# SCH_Glucosan2-DetectorSide.net
KiCad netlist of a schematic drawn in EasyEDA
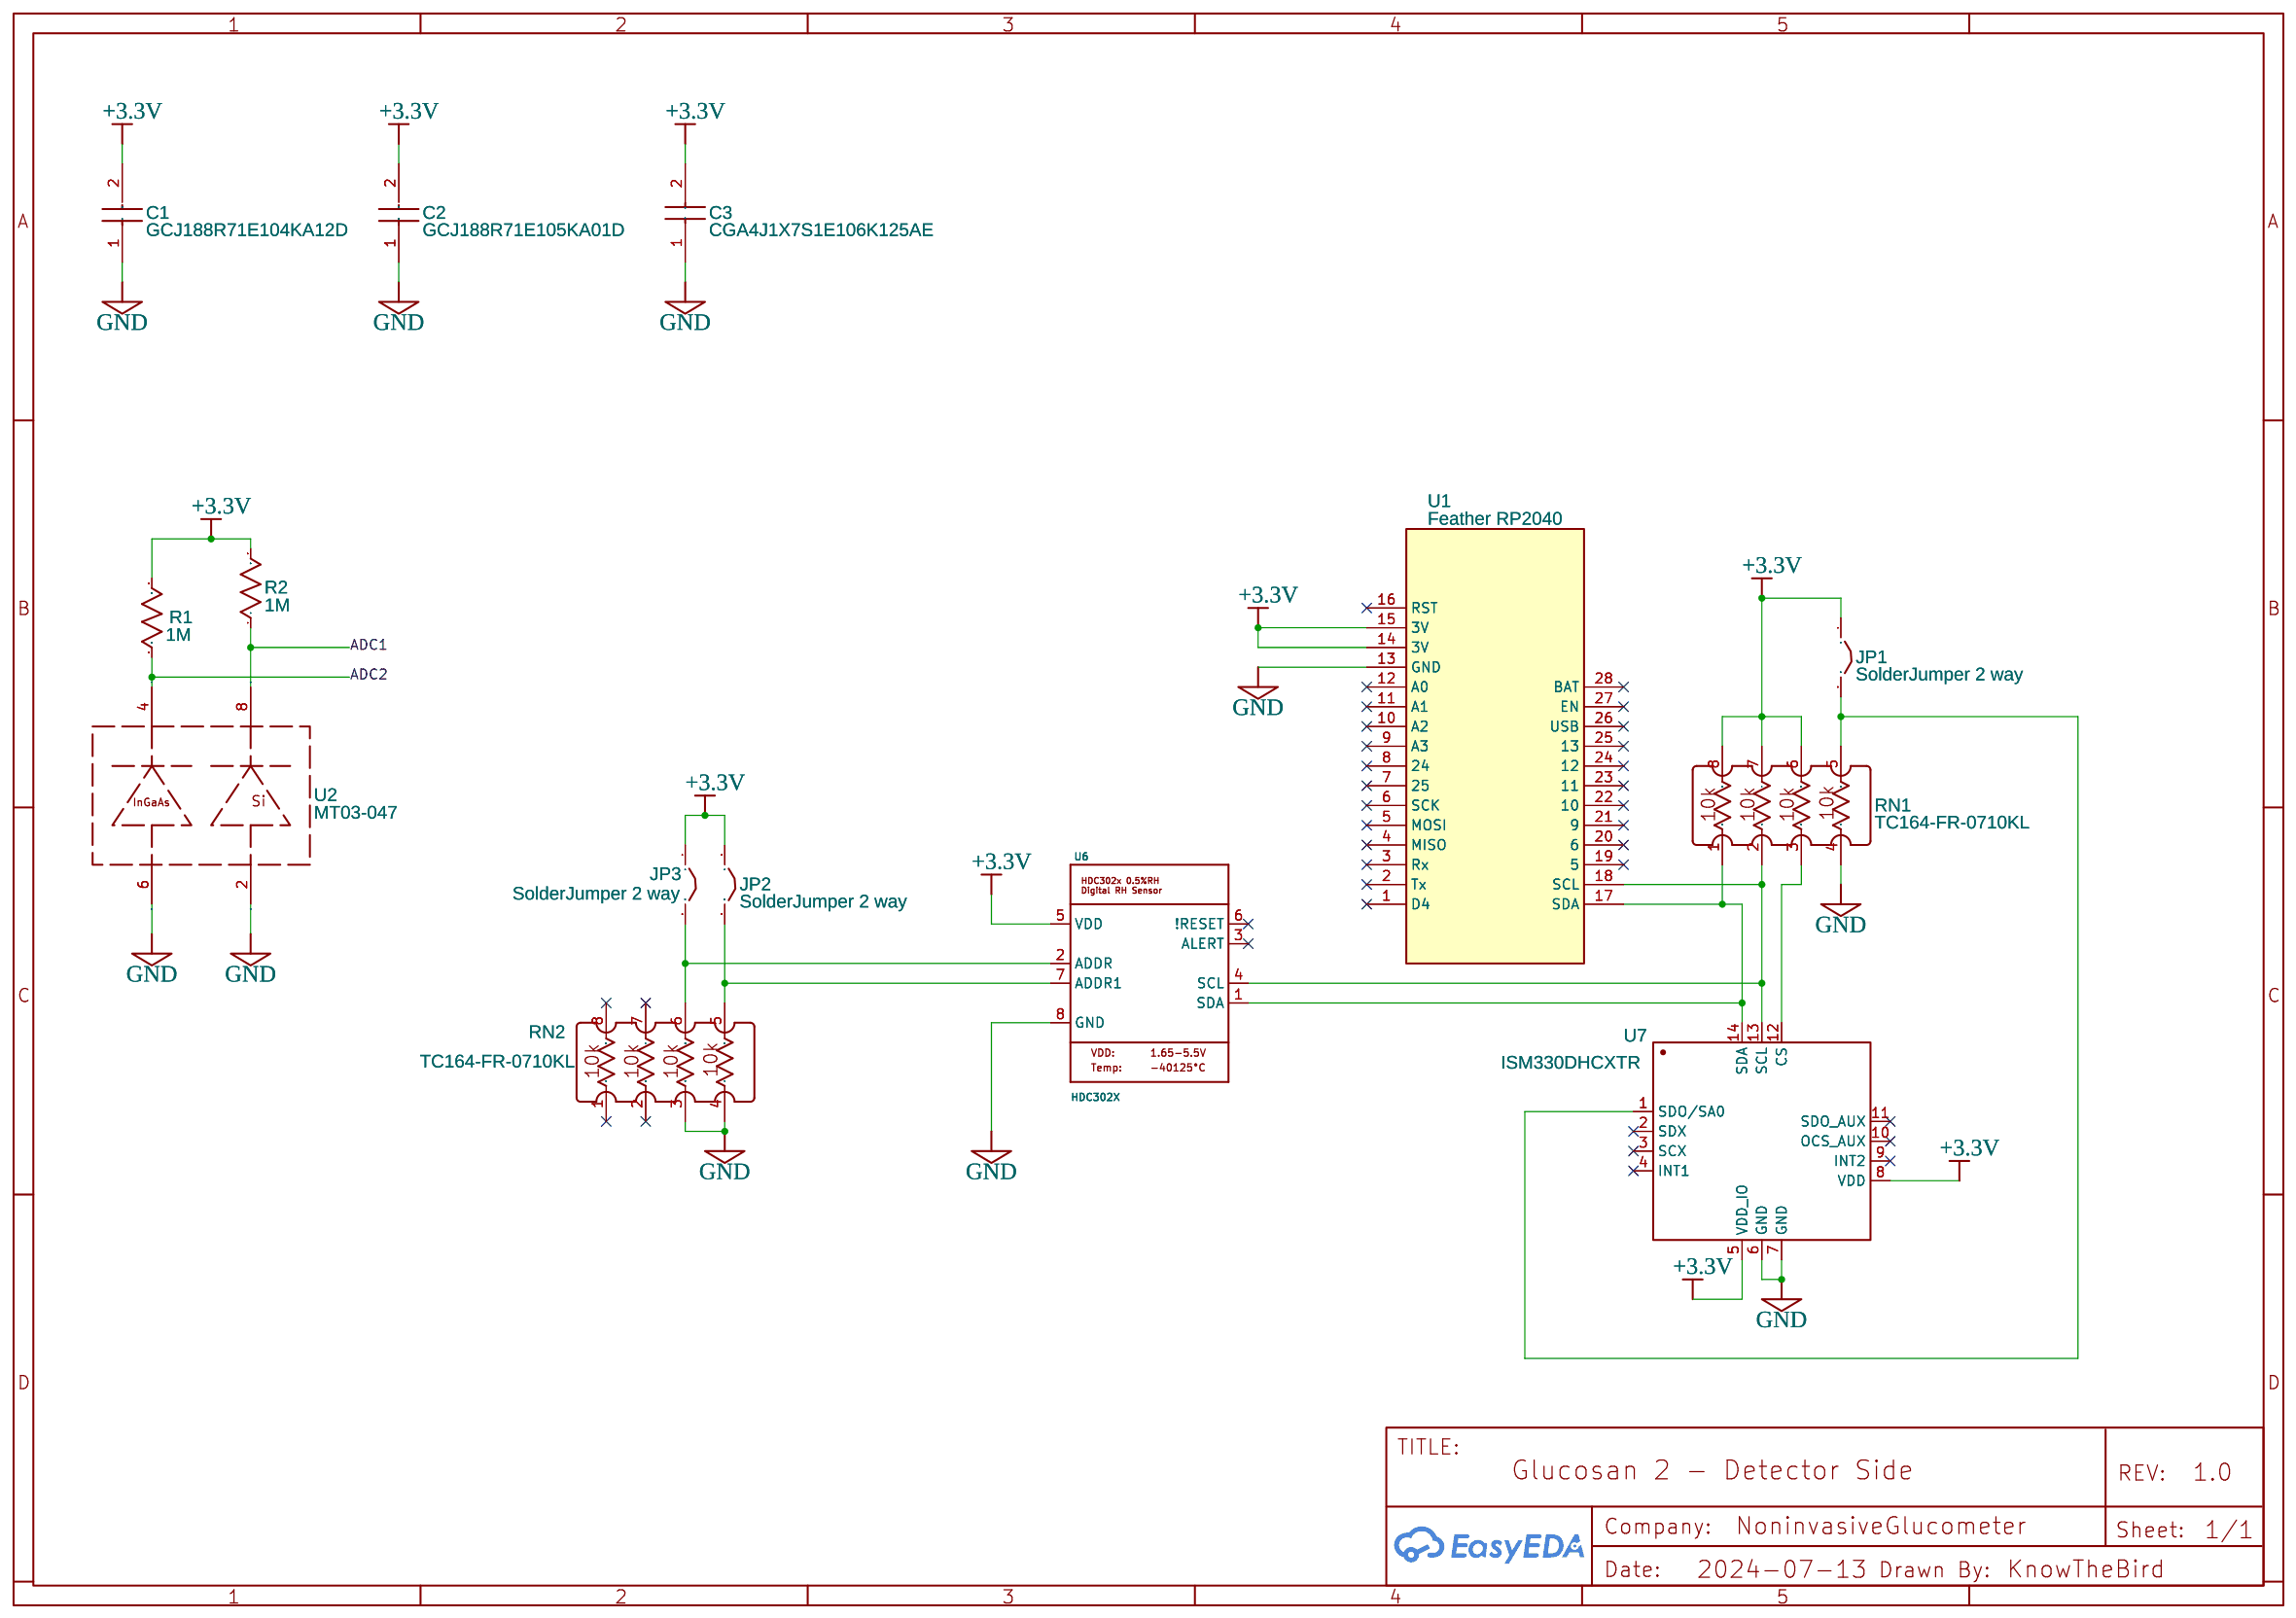
[diagram p0: schematic sheet]

(export (version "E")
  (design (tool "Eeschema 10.0.6"))
  (components
    (comp (ref "C1") (value "GCJ188R71E104KA12D") (libsource (lib "") (part "GCJ188R71E104KA12D")))
    (comp (ref "C2") (value "GCJ188R71E105KA01D") (libsource (lib "") (part "GCJ188R71E105KA01D")))
    (comp (ref "C3") (value "CGA4J1X7S1E106K125AE") (libsource (lib "") (part "CGA4J1X7S1E106K125AE")))
    (comp (ref "JP1") (value "SolderJumper 2 way") (libsource (lib "") (part "Jumper Solder Bridge SMD")))
    (comp (ref "JP2") (value "SolderJumper 2 way") (libsource (lib "") (part "Jumper Solder Bridge SMD")))
    (comp (ref "JP3") (value "SolderJumper 2 way") (libsource (lib "") (part "Jumper Solder Bridge SMD")))
    (comp (ref "R1") (value "1M") (libsource (lib "") (part "R_0603_US")))
    (comp (ref "R2") (value "1M") (libsource (lib "") (part "R_0603_US")))
    (comp (ref "RN1")
      (value "TC164-FR-0710KL")
      (fields (field (name "Manufacturer") "Yageo"))
      (libsource (lib "") (part "TC164-FR-0710KL"))
    )
    (comp (ref "RN2")
      (value "TC164-FR-0710KL")
      (fields (field (name "Manufacturer") "Yageo"))
      (libsource (lib "") (part "TC164-FR-0710KL"))
    )
    (comp (ref "U1")
      (value "Feather RP2040")
      (fields (field (name "Manufacturer") "Adafruit"))
      (libsource (lib "") (part "Feather RP2040"))
    )
    (comp (ref "U2")
      (value "MT03-047")
      (fields (field (name "Manufacturer") "Marktech Optoelectronics"))
      (libsource (lib "") (part "MT03-047"))
    )
    (comp (ref "U6") (value "HDC302X") (libsource (lib "") (part "Unknown_575_-325")))
    (comp (ref "U7")
      (value "ISM330DHCXTR")
      (fields (field (name "Manufacturer") "ST(意法半导体)"))
      (libsource (lib "") (part "ISM330DHCXTR"))
    )
  )
  (nets
    (net (code "1") (name "+3.3V") (class "Default")
      (node (ref "C1") (pin "2") (pinfunction "2_2") (pintype "bidirectional"))
      (node (ref "C2") (pin "2") (pinfunction "2_2") (pintype "bidirectional"))
      (node (ref "C3") (pin "2") (pinfunction "2_2") (pintype "unspecified"))
      (node (ref "JP1") (pin "1") (pinfunction "1_1") (pintype "unspecified"))
      (node (ref "JP2") (pin "1") (pinfunction "1_1") (pintype "unspecified"))
      (node (ref "JP3") (pin "1") (pinfunction "1_1") (pintype "unspecified"))
      (node (ref "R1") (pin "2") (pinfunction "2_2") (pintype "unspecified"))
      (node (ref "R2") (pin "2") (pinfunction "2_2") (pintype "unspecified"))
      (node (ref "RN1") (pin "6") (pinfunction "6_6") (pintype "unspecified"))
      (node (ref "RN1") (pin "7") (pinfunction "7_7") (pintype "unspecified"))
      (node (ref "RN1") (pin "8") (pinfunction "8_8") (pintype "unspecified"))
      (node (ref "U1") (pin "14") (pinfunction "3V_14") (pintype "unspecified"))
      (node (ref "U1") (pin "15") (pinfunction "3V_15") (pintype "unspecified"))
      (node (ref "U6") (pin "5") (pinfunction "VDD_5") (pintype "bidirectional"))
      (node (ref "U7") (pin "5") (pinfunction "VDD_IO_5") (pintype "unspecified"))
      (node (ref "U7") (pin "8") (pinfunction "VDD_8") (pintype "unspecified"))
    )
    (net (code "2") (name "/ADC1") (class "Default")
      (node (ref "R2") (pin "1") (pinfunction "1_1") (pintype "unspecified"))
      (node (ref "U2") (pin "8") (pinfunction "8_8") (pintype "unspecified"))
    )
    (net (code "3") (name "/ADC2") (class "Default")
      (node (ref "R1") (pin "1") (pinfunction "1_1") (pintype "unspecified"))
      (node (ref "U2") (pin "4") (pinfunction "4_4") (pintype "unspecified"))
    )
    (net (code "4") (name "GND") (class "Default")
      (node (ref "C1") (pin "1") (pinfunction "1_1") (pintype "bidirectional"))
      (node (ref "C2") (pin "1") (pinfunction "1_1") (pintype "bidirectional"))
      (node (ref "C3") (pin "1") (pinfunction "1_1") (pintype "unspecified"))
      (node (ref "RN1") (pin "4") (pinfunction "4_4") (pintype "unspecified"))
      (node (ref "RN2") (pin "3") (pinfunction "3_3") (pintype "unspecified"))
      (node (ref "RN2") (pin "4") (pinfunction "4_4") (pintype "unspecified"))
      (node (ref "U1") (pin "13") (pinfunction "GND_13") (pintype "unspecified"))
      (node (ref "U2") (pin "2") (pinfunction "2_2") (pintype "unspecified"))
      (node (ref "U2") (pin "6") (pinfunction "6_6") (pintype "unspecified"))
      (node (ref "U6") (pin "8") (pinfunction "GND_8") (pintype "bidirectional"))
      (node (ref "U7") (pin "6") (pinfunction "GND_6") (pintype "unspecified"))
      (node (ref "U7") (pin "7") (pinfunction "GND_7") (pintype "unspecified"))
    )
    (net (code "5") (name "Net-(U1-SCL)") (class "Default")
      (node (ref "RN1") (pin "2") (pinfunction "2_2") (pintype "unspecified"))
      (node (ref "U1") (pin "18") (pinfunction "SCL_18") (pintype "unspecified"))
      (node (ref "U6") (pin "4") (pinfunction "SCL_4") (pintype "bidirectional"))
      (node (ref "U7") (pin "13") (pinfunction "SCL_13") (pintype "unspecified"))
    )
    (net (code "6") (name "Net-(U1-SDA)") (class "Default")
      (node (ref "RN1") (pin "1") (pinfunction "1_1") (pintype "unspecified"))
      (node (ref "U1") (pin "17") (pinfunction "SDA_17") (pintype "unspecified"))
      (node (ref "U6") (pin "1") (pinfunction "SDA_1") (pintype "bidirectional"))
      (node (ref "U7") (pin "14") (pinfunction "SDA_14") (pintype "unspecified"))
    )
    (net (code "7") (name "Net-(U6-ADDR)") (class "Default")
      (node (ref "JP3") (pin "2") (pinfunction "2_2") (pintype "unspecified"))
      (node (ref "RN2") (pin "6") (pinfunction "6_6") (pintype "unspecified"))
      (node (ref "U6") (pin "2") (pinfunction "ADDR_2") (pintype "bidirectional"))
    )
    (net (code "8") (name "Net-(U6-ADDR1)") (class "Default")
      (node (ref "JP2") (pin "2") (pinfunction "2_2") (pintype "unspecified"))
      (node (ref "RN2") (pin "5") (pinfunction "5_5") (pintype "unspecified"))
      (node (ref "U6") (pin "7") (pinfunction "ADDR1_7") (pintype "bidirectional"))
    )
    (net (code "9") (name "Net-(U7-CS)") (class "Default")
      (node (ref "RN1") (pin "3") (pinfunction "3_3") (pintype "unspecified"))
      (node (ref "U7") (pin "12") (pinfunction "CS_12") (pintype "unspecified"))
    )
    (net (code "10") (name "Net-(U7-SDO{slash}SA0)") (class "Default")
      (node (ref "JP1") (pin "2") (pinfunction "2_2") (pintype "unspecified"))
      (node (ref "RN1") (pin "5") (pinfunction "5_5") (pintype "unspecified"))
      (node (ref "U7") (pin "1") (pinfunction "SDO/SA0_1") (pintype "unspecified"))
    )
    (net (code "11") (name "unconnected-(RN2-Pad1)") (class "Default")
      (node (ref "RN2") (pin "1") (pinfunction "1_1") (pintype "unspecified+no_connect"))
    )
    (net (code "12") (name "unconnected-(RN2-Pad2)") (class "Default")
      (node (ref "RN2") (pin "2") (pinfunction "2_2") (pintype "unspecified+no_connect"))
    )
    (net (code "13") (name "unconnected-(RN2-Pad7)") (class "Default")
      (node (ref "RN2") (pin "7") (pinfunction "7_7") (pintype "unspecified+no_connect"))
    )
    (net (code "14") (name "unconnected-(RN2-Pad8)") (class "Default")
      (node (ref "RN2") (pin "8") (pinfunction "8_8") (pintype "unspecified+no_connect"))
    )
    (net (code "15") (name "unconnected-(U1-5-Pad19)") (class "Default")
      (node (ref "U1") (pin "19") (pinfunction "5_19") (pintype "unspecified+no_connect"))
    )
    (net (code "16") (name "unconnected-(U1-6-Pad20)") (class "Default")
      (node (ref "U1") (pin "20") (pinfunction "6_20") (pintype "unspecified+no_connect"))
    )
    (net (code "17") (name "unconnected-(U1-9-Pad21)") (class "Default")
      (node (ref "U1") (pin "21") (pinfunction "9_21") (pintype "unspecified+no_connect"))
    )
    (net (code "18") (name "unconnected-(U1-10-Pad22)") (class "Default")
      (node (ref "U1") (pin "22") (pinfunction "10_22") (pintype "unspecified+no_connect"))
    )
    (net (code "19") (name "unconnected-(U1-11-Pad23)") (class "Default")
      (node (ref "U1") (pin "23") (pinfunction "11_23") (pintype "unspecified+no_connect"))
    )
    (net (code "20") (name "unconnected-(U1-12-Pad24)") (class "Default")
      (node (ref "U1") (pin "24") (pinfunction "12_24") (pintype "unspecified+no_connect"))
    )
    (net (code "21") (name "unconnected-(U1-13-Pad25)") (class "Default")
      (node (ref "U1") (pin "25") (pinfunction "13_25") (pintype "unspecified+no_connect"))
    )
    (net (code "22") (name "unconnected-(U1-24-Pad8)") (class "Default")
      (node (ref "U1") (pin "8") (pinfunction "24_8") (pintype "unspecified+no_connect"))
    )
    (net (code "23") (name "unconnected-(U1-25-Pad7)") (class "Default")
      (node (ref "U1") (pin "7") (pinfunction "25_7") (pintype "unspecified+no_connect"))
    )
    (net (code "24") (name "unconnected-(U1-A0-Pad12)") (class "Default")
      (node (ref "U1") (pin "12") (pinfunction "A0_12") (pintype "unspecified+no_connect"))
    )
    (net (code "25") (name "unconnected-(U1-A1-Pad11)") (class "Default")
      (node (ref "U1") (pin "11") (pinfunction "A1_11") (pintype "unspecified+no_connect"))
    )
    (net (code "26") (name "unconnected-(U1-A2-Pad10)") (class "Default")
      (node (ref "U1") (pin "10") (pinfunction "A2_10") (pintype "unspecified+no_connect"))
    )
    (net (code "27") (name "unconnected-(U1-A3-Pad9)") (class "Default")
      (node (ref "U1") (pin "9") (pinfunction "A3_9") (pintype "unspecified+no_connect"))
    )
    (net (code "28") (name "unconnected-(U1-BAT-Pad28)") (class "Default")
      (node (ref "U1") (pin "28") (pinfunction "BAT_28") (pintype "unspecified+no_connect"))
    )
    (net (code "29") (name "unconnected-(U1-D4-Pad1)") (class "Default")
      (node (ref "U1") (pin "1") (pinfunction "D4_1") (pintype "unspecified+no_connect"))
    )
    (net (code "30") (name "unconnected-(U1-EN-Pad27)") (class "Default")
      (node (ref "U1") (pin "27") (pinfunction "EN_27") (pintype "unspecified+no_connect"))
    )
    (net (code "31") (name "unconnected-(U1-MISO-Pad4)") (class "Default")
      (node (ref "U1") (pin "4") (pinfunction "MISO_4") (pintype "unspecified+no_connect"))
    )
    (net (code "32") (name "unconnected-(U1-MOSI-Pad5)") (class "Default")
      (node (ref "U1") (pin "5") (pinfunction "MOSI_5") (pintype "unspecified+no_connect"))
    )
    (net (code "33") (name "unconnected-(U1-RST-Pad16)") (class "Default")
      (node (ref "U1") (pin "16") (pinfunction "RST_16") (pintype "unspecified+no_connect"))
    )
    (net (code "34") (name "unconnected-(U1-Rx-Pad3)") (class "Default")
      (node (ref "U1") (pin "3") (pinfunction "Rx_3") (pintype "unspecified+no_connect"))
    )
    (net (code "35") (name "unconnected-(U1-SCK-Pad6)") (class "Default")
      (node (ref "U1") (pin "6") (pinfunction "SCK_6") (pintype "unspecified+no_connect"))
    )
    (net (code "36") (name "unconnected-(U1-Tx-Pad2)") (class "Default")
      (node (ref "U1") (pin "2") (pinfunction "Tx_2") (pintype "unspecified+no_connect"))
    )
    (net (code "37") (name "unconnected-(U1-USB-Pad26)") (class "Default")
      (node (ref "U1") (pin "26") (pinfunction "USB_26") (pintype "unspecified+no_connect"))
    )
    (net (code "38") (name "unconnected-(U6-!RESET-Pad6)") (class "Default")
      (node (ref "U6") (pin "6") (pinfunction "!RESET_6") (pintype "bidirectional+no_connect"))
    )
    (net (code "39") (name "unconnected-(U6-ALERT-Pad3)") (class "Default")
      (node (ref "U6") (pin "3") (pinfunction "ALERT_3") (pintype "bidirectional+no_connect"))
    )
    (net (code "40") (name "unconnected-(U7-INT1-Pad4)") (class "Default")
      (node (ref "U7") (pin "4") (pinfunction "INT1_4") (pintype "unspecified+no_connect"))
    )
    (net (code "41") (name "unconnected-(U7-INT2-Pad9)") (class "Default")
      (node (ref "U7") (pin "9") (pinfunction "INT2_9") (pintype "unspecified+no_connect"))
    )
    (net (code "42") (name "unconnected-(U7-OCS_AUX-Pad10)") (class "Default")
      (node (ref "U7") (pin "10") (pinfunction "OCS_AUX_10") (pintype "unspecified+no_connect"))
    )
    (net (code "43") (name "unconnected-(U7-SCX-Pad3)") (class "Default")
      (node (ref "U7") (pin "3") (pinfunction "SCX_3") (pintype "unspecified+no_connect"))
    )
    (net (code "44") (name "unconnected-(U7-SDO_AUX-Pad11)") (class "Default")
      (node (ref "U7") (pin "11") (pinfunction "SDO_AUX_11") (pintype "unspecified+no_connect"))
    )
    (net (code "45") (name "unconnected-(U7-SDX-Pad2)") (class "Default")
      (node (ref "U7") (pin "2") (pinfunction "SDX_2") (pintype "unspecified+no_connect"))
    )
  )
)
